# Microcontroller_and_Memory.net
KiCad netlist of a schematic drawn in Altium Designer
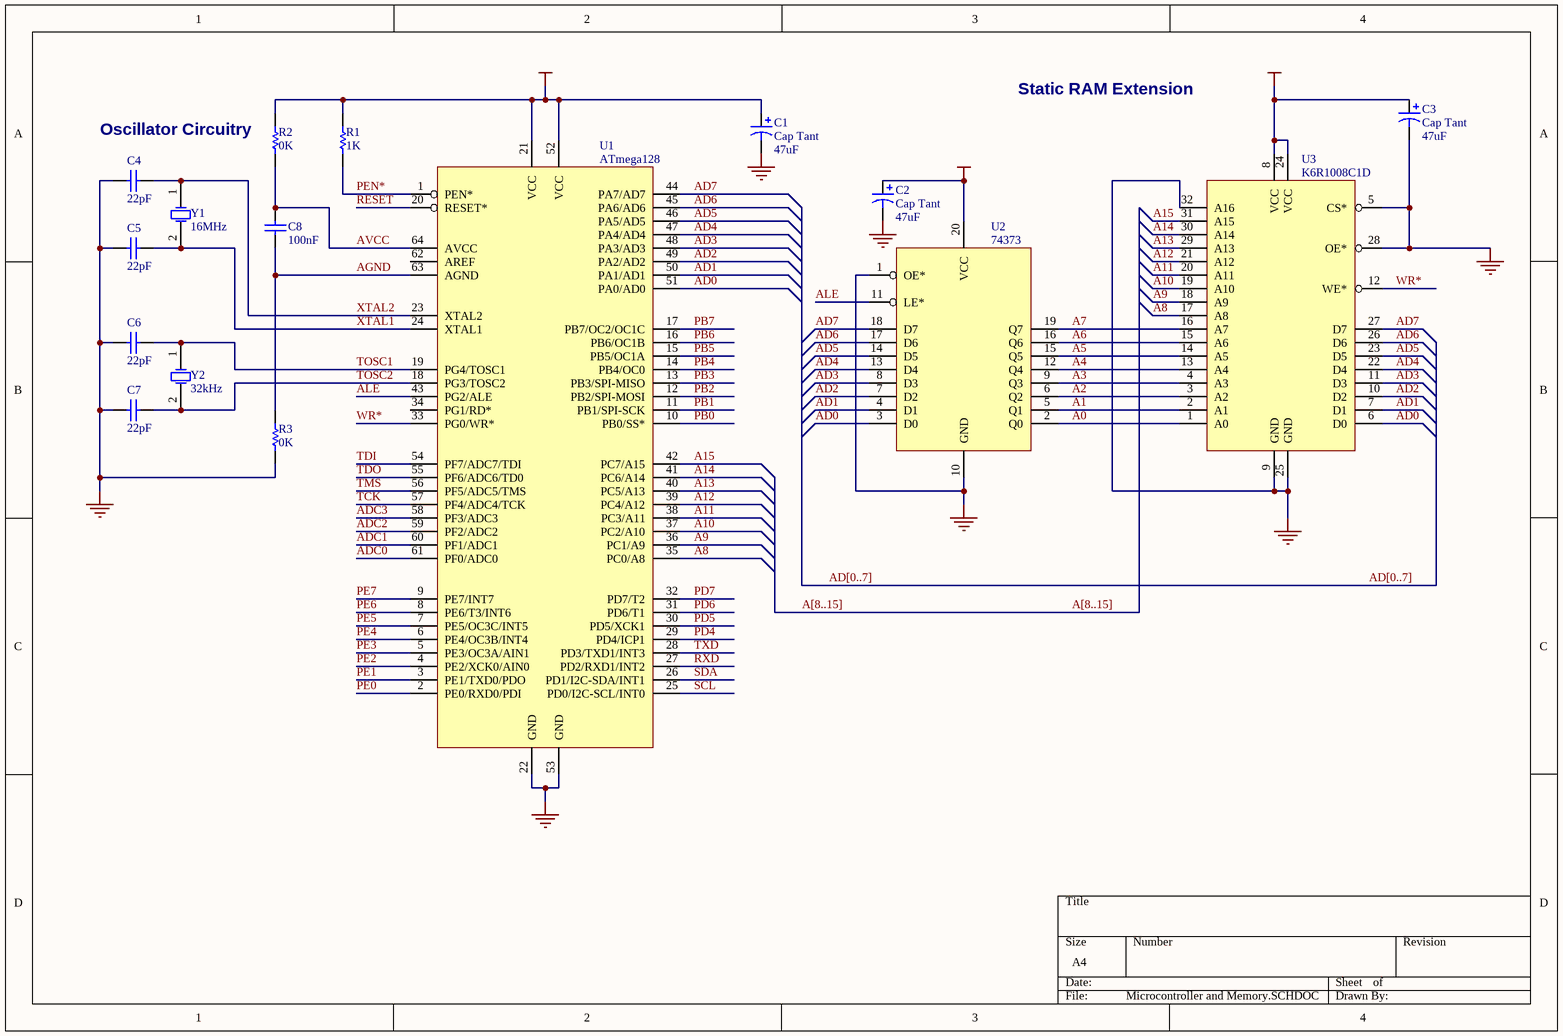
[diagram p0: Microcontroller and Memory.SCHDOC]

(export (version "E")
  (design (tool "Eeschema 10.0.6"))
  (components
    (comp (ref "C1")
      (value "Cap Tant")
      (footprint "CAPR5-4X5")
      (description "Polarized Capacitor (Axial)")
      (fields (field (name "ALTIUM_VALUE") "47uF") (field (name "PUBLISHER") "Altium Limited"))
      (libsource (lib "Miscellaneous Devices") (part "Cap Pol2"))
    )
    (comp (ref "C2")
      (value "Cap Tant")
      (footprint "CAPR5-4X5")
      (description "Polarized Capacitor (Axial)")
      (fields (field (name "ALTIUM_VALUE") "47uF") (field (name "PUBLISHER") "Altium Limited"))
      (libsource (lib "Miscellaneous Devices") (part "Cap Pol2"))
    )
    (comp (ref "C3")
      (value "Cap Tant")
      (footprint "CAPR5-4X5")
      (description "Polarized Capacitor (Axial)")
      (fields (field (name "ALTIUM_VALUE") "47uF") (field (name "PUBLISHER") "Altium Limited"))
      (libsource (lib "Miscellaneous Devices") (part "Cap Pol2"))
    )
    (comp (ref "C4")
      (value "22pF")
      (footprint "BCY-W2/D3.1")
      (description "Capacitor")
      (fields (field (name "PUBLISHER") "Altium Limited"))
      (libsource (lib "Miscellaneous Devices") (part "Cap"))
    )
    (comp (ref "C5")
      (value "22pF")
      (footprint "BCY-W2/D3.1")
      (description "Capacitor")
      (fields (field (name "PUBLISHER") "Altium Limited"))
      (libsource (lib "Miscellaneous Devices") (part "Cap"))
    )
    (comp (ref "C6")
      (value "22pF")
      (footprint "BCY-W2/D3.1")
      (description "Capacitor")
      (fields (field (name "PUBLISHER") "Altium Limited"))
      (libsource (lib "Miscellaneous Devices") (part "Cap"))
    )
    (comp (ref "C7")
      (value "22pF")
      (footprint "BCY-W2/D3.1")
      (description "Capacitor")
      (fields (field (name "PUBLISHER") "Altium Limited"))
      (libsource (lib "Miscellaneous Devices") (part "Cap"))
    )
    (comp (ref "C8")
      (value "100nF")
      (footprint "BCY-W2/D3.1")
      (description "Capacitor")
      (fields (field (name "PUBLISHER") "Altium Limited"))
      (libsource (lib "Miscellaneous Devices") (part "Cap"))
    )
    (comp (ref "R1")
      (value "1K")
      (footprint "AXIAL-0.3")
      (description "Resistor")
      (fields (field (name "PUBLISHER") "Altium Limited"))
      (libsource (lib "Miscellaneous Devices") (part "Res1"))
    )
    (comp (ref "R2")
      (value "0K")
      (footprint "AXIAL-0.3")
      (description "Resistor")
      (fields (field (name "PUBLISHER") "Altium Limited"))
      (libsource (lib "Miscellaneous Devices") (part "Res1"))
    )
    (comp (ref "R3")
      (value "0K")
      (footprint "AXIAL-0.3")
      (description "Resistor")
      (fields (field (name "PUBLISHER") "Altium Limited"))
      (libsource (lib "Miscellaneous Devices") (part "Res1"))
    )
    (comp (ref "U1")
      (value "ATmega128")
      (footprint "QFP (~0.8mm Pitch, Square) - Corner Index:QFP14x14-G64/Y1.4N")
      (description "Atmel ATmega128 MCU")
      (libsource (lib "*") (part "ATmega128"))
    )
    (comp (ref "U2")
      (value "74373")
      (footprint "SO-G20/Y1.45")
      (description "Octal 8-bit D-type Latch")
      (libsource (lib "Schematic Library") (part "74373"))
    )
    (comp (ref "U3")
      (value "K6R1008C1D")
      (footprint "SO-G32/Y1.45")
      (description "Samsung 128Kx8 High-Speed Static RAM")
      (libsource (lib "Schematic Library") (part "K6R1008C1D"))
    )
    (comp (ref "Y1")
      (value "16MHz")
      (footprint "BCY-W2/D3.1")
      (description "Crystal Oscillator")
      (fields (field (name "PUBLISHER") "Altium Limited"))
      (libsource (lib "Miscellaneous Devices") (part "XTAL"))
    )
    (comp (ref "Y2")
      (value "32kHz")
      (footprint "BCY-W2/D3.1")
      (description "Crystal Oscillator")
      (fields (field (name "PUBLISHER") "Altium Limited"))
      (libsource (lib "Miscellaneous Devices") (part "XTAL"))
    )
  )
  (nets
    (net (code "1") (name "/A0") (class "Default")
      (node (ref "U2") (pin "2") (pinfunction "Q0_2") (pintype "passive"))
      (node (ref "U3") (pin "1") (pinfunction "A0_1") (pintype "passive"))
    )
    (net (code "2") (name "/A1") (class "Default")
      (node (ref "U2") (pin "5") (pinfunction "Q1_5") (pintype "passive"))
      (node (ref "U3") (pin "2") (pinfunction "A1_2") (pintype "passive"))
    )
    (net (code "3") (name "/A2") (class "Default")
      (node (ref "U2") (pin "6") (pinfunction "Q2_6") (pintype "passive"))
      (node (ref "U3") (pin "3") (pinfunction "A2_3") (pintype "passive"))
    )
    (net (code "4") (name "/A3") (class "Default")
      (node (ref "U2") (pin "9") (pinfunction "Q3_9") (pintype "passive"))
      (node (ref "U3") (pin "4") (pinfunction "A3_4") (pintype "passive"))
    )
    (net (code "5") (name "/A4") (class "Default")
      (node (ref "U2") (pin "12") (pinfunction "Q4_12") (pintype "passive"))
      (node (ref "U3") (pin "13") (pinfunction "A4_13") (pintype "passive"))
    )
    (net (code "6") (name "/A5") (class "Default")
      (node (ref "U2") (pin "15") (pinfunction "Q5_15") (pintype "passive"))
      (node (ref "U3") (pin "14") (pinfunction "A5_14") (pintype "passive"))
    )
    (net (code "7") (name "/A6") (class "Default")
      (node (ref "U2") (pin "16") (pinfunction "Q6_16") (pintype "passive"))
      (node (ref "U3") (pin "15") (pinfunction "A6_15") (pintype "passive"))
    )
    (net (code "8") (name "/A7") (class "Default")
      (node (ref "U2") (pin "19") (pinfunction "Q7_19") (pintype "passive"))
      (node (ref "U3") (pin "16") (pinfunction "A7_16") (pintype "passive"))
    )
    (net (code "9") (name "/A8") (class "Default")
      (node (ref "U1") (pin "35") (pinfunction "PC0/A8_35") (pintype "passive"))
      (node (ref "U3") (pin "17") (pinfunction "A8_17") (pintype "passive"))
    )
    (net (code "10") (name "/A9") (class "Default")
      (node (ref "U1") (pin "36") (pinfunction "PC1/A9_36") (pintype "passive"))
      (node (ref "U3") (pin "18") (pinfunction "A9_18") (pintype "passive"))
    )
    (net (code "11") (name "/A10") (class "Default")
      (node (ref "U1") (pin "37") (pinfunction "PC2/A10_37") (pintype "passive"))
      (node (ref "U3") (pin "19") (pinfunction "A10_19") (pintype "passive"))
    )
    (net (code "12") (name "/A11") (class "Default")
      (node (ref "U1") (pin "38") (pinfunction "PC3/A11_38") (pintype "passive"))
      (node (ref "U3") (pin "20") (pinfunction "A11_20") (pintype "passive"))
    )
    (net (code "13") (name "/A12") (class "Default")
      (node (ref "U1") (pin "39") (pinfunction "PC4/A12_39") (pintype "passive"))
      (node (ref "U3") (pin "21") (pinfunction "A12_21") (pintype "passive"))
    )
    (net (code "14") (name "/A13") (class "Default")
      (node (ref "U1") (pin "40") (pinfunction "PC5/A13_40") (pintype "passive"))
      (node (ref "U3") (pin "29") (pinfunction "A13_29") (pintype "passive"))
    )
    (net (code "15") (name "/A14") (class "Default")
      (node (ref "U1") (pin "41") (pinfunction "PC6/A14_41") (pintype "passive"))
      (node (ref "U3") (pin "30") (pinfunction "A14_30") (pintype "passive"))
    )
    (net (code "16") (name "/A15") (class "Default")
      (node (ref "U1") (pin "42") (pinfunction "PC7/A15_42") (pintype "passive"))
      (node (ref "U3") (pin "31") (pinfunction "A15_31") (pintype "passive"))
    )
    (net (code "17") (name "/AD0") (class "Default")
      (node (ref "U1") (pin "51") (pinfunction "PA0/AD0_51") (pintype "passive"))
      (node (ref "U2") (pin "3") (pinfunction "D0_3") (pintype "passive"))
      (node (ref "U3") (pin "6") (pinfunction "D0_6") (pintype "passive"))
    )
    (net (code "18") (name "/AD1") (class "Default")
      (node (ref "U1") (pin "50") (pinfunction "PA1/AD1_50") (pintype "passive"))
      (node (ref "U2") (pin "4") (pinfunction "D1_4") (pintype "passive"))
      (node (ref "U3") (pin "7") (pinfunction "D1_7") (pintype "passive"))
    )
    (net (code "19") (name "/AD2") (class "Default")
      (node (ref "U1") (pin "49") (pinfunction "PA2/AD2_49") (pintype "passive"))
      (node (ref "U2") (pin "7") (pinfunction "D2_7") (pintype "passive"))
      (node (ref "U3") (pin "10") (pinfunction "D2_10") (pintype "passive"))
    )
    (net (code "20") (name "/AD3") (class "Default")
      (node (ref "U1") (pin "48") (pinfunction "PA3/AD3_48") (pintype "passive"))
      (node (ref "U2") (pin "8") (pinfunction "D3_8") (pintype "passive"))
      (node (ref "U3") (pin "11") (pinfunction "D3_11") (pintype "passive"))
    )
    (net (code "21") (name "/AD4") (class "Default")
      (node (ref "U1") (pin "47") (pinfunction "PA4/AD4_47") (pintype "passive"))
      (node (ref "U2") (pin "13") (pinfunction "D4_13") (pintype "passive"))
      (node (ref "U3") (pin "22") (pinfunction "D4_22") (pintype "passive"))
    )
    (net (code "22") (name "/AD5") (class "Default")
      (node (ref "U1") (pin "46") (pinfunction "PA5/AD5_46") (pintype "passive"))
      (node (ref "U2") (pin "14") (pinfunction "D5_14") (pintype "passive"))
      (node (ref "U3") (pin "23") (pinfunction "D5_23") (pintype "passive"))
    )
    (net (code "23") (name "/AD6") (class "Default")
      (node (ref "U1") (pin "45") (pinfunction "PA6/AD6_45") (pintype "passive"))
      (node (ref "U2") (pin "17") (pinfunction "D6_17") (pintype "passive"))
      (node (ref "U3") (pin "26") (pinfunction "D6_26") (pintype "passive"))
    )
    (net (code "24") (name "/AD7") (class "Default")
      (node (ref "U1") (pin "44") (pinfunction "PA7/AD7_44") (pintype "passive"))
      (node (ref "U2") (pin "18") (pinfunction "D7_18") (pintype "passive"))
      (node (ref "U3") (pin "27") (pinfunction "D7_27") (pintype "passive"))
    )
    (net (code "25") (name "/ADC0") (class "Default")
      (node (ref "U1") (pin "61") (pinfunction "PF0/ADC0_61") (pintype "passive"))
    )
    (net (code "26") (name "/ADC1") (class "Default")
      (node (ref "U1") (pin "60") (pinfunction "PF1/ADC1_60") (pintype "passive"))
    )
    (net (code "27") (name "/ADC2") (class "Default")
      (node (ref "U1") (pin "59") (pinfunction "PF2/ADC2_59") (pintype "passive"))
    )
    (net (code "28") (name "/ADC3") (class "Default")
      (node (ref "U1") (pin "58") (pinfunction "PF3/ADC3_58") (pintype "passive"))
    )
    (net (code "30") (name "/AGND") (class "Default")
      (node (ref "C8") (pin "1") (pinfunction "1_1") (pintype "passive"))
      (node (ref "R3") (pin "2") (pinfunction "2_2") (pintype "passive"))
      (node (ref "U1") (pin "63") (pinfunction "AGND_63") (pintype "passive"))
    )
    (net (code "31") (name "/ALE") (class "Default")
      (node (ref "U1") (pin "43") (pinfunction "PG2/ALE_43") (pintype "passive"))
      (node (ref "U2") (pin "11") (pinfunction "LE*_11") (pintype "passive"))
    )
    (net (code "32") (name "/AVCC") (class "Default")
      (node (ref "C8") (pin "2") (pinfunction "2_2") (pintype "passive"))
      (node (ref "R2") (pin "1") (pinfunction "1_1") (pintype "passive"))
      (node (ref "U1") (pin "64") (pinfunction "AVCC_64") (pintype "passive"))
    )
    (net (code "34") (name "/PB0") (class "Default")
      (node (ref "U1") (pin "10") (pinfunction "PB0/SS*_10") (pintype "passive"))
    )
    (net (code "35") (name "/PB1") (class "Default")
      (node (ref "U1") (pin "11") (pinfunction "PB1/SPI-SCK_11") (pintype "passive"))
    )
    (net (code "36") (name "/PB2") (class "Default")
      (node (ref "U1") (pin "12") (pinfunction "PB2/SPI-MOSI_12") (pintype "passive"))
    )
    (net (code "37") (name "/PB3") (class "Default")
      (node (ref "U1") (pin "13") (pinfunction "PB3/SPI-MISO_13") (pintype "passive"))
    )
    (net (code "38") (name "/PB4") (class "Default")
      (node (ref "U1") (pin "14") (pinfunction "PB4/OC0_14") (pintype "passive"))
    )
    (net (code "39") (name "/PB5") (class "Default")
      (node (ref "U1") (pin "15") (pinfunction "PB5/OC1A_15") (pintype "passive"))
    )
    (net (code "40") (name "/PB6") (class "Default")
      (node (ref "U1") (pin "16") (pinfunction "PB6/OC1B_16") (pintype "passive"))
    )
    (net (code "41") (name "/PB7") (class "Default")
      (node (ref "U1") (pin "17") (pinfunction "PB7/OC2/OC1C_17") (pintype "passive"))
    )
    (net (code "42") (name "/PD4") (class "Default")
      (node (ref "U1") (pin "29") (pinfunction "PD4/ICP1_29") (pintype "passive"))
    )
    (net (code "43") (name "/PD5") (class "Default")
      (node (ref "U1") (pin "30") (pinfunction "PD5/XCK1_30") (pintype "passive"))
    )
    (net (code "44") (name "/PD6") (class "Default")
      (node (ref "U1") (pin "31") (pinfunction "PD6/T1_31") (pintype "passive"))
    )
    (net (code "45") (name "/PD7") (class "Default")
      (node (ref "U1") (pin "32") (pinfunction "PD7/T2_32") (pintype "passive"))
    )
    (net (code "46") (name "/PE0") (class "Default")
      (node (ref "U1") (pin "2") (pinfunction "PE0/RXD0/PDI_2") (pintype "passive"))
    )
    (net (code "47") (name "/PE1") (class "Default")
      (node (ref "U1") (pin "3") (pinfunction "PE1/TXD0/PDO_3") (pintype "passive"))
    )
    (net (code "48") (name "/PE2") (class "Default")
      (node (ref "U1") (pin "4") (pinfunction "PE2/XCK0/AIN0_4") (pintype "passive"))
    )
    (net (code "49") (name "/PE3") (class "Default")
      (node (ref "U1") (pin "5") (pinfunction "PE3/OC3A/AIN1_5") (pintype "passive"))
    )
    (net (code "50") (name "/PE4") (class "Default")
      (node (ref "U1") (pin "6") (pinfunction "PE4/OC3B/INT4_6") (pintype "passive"))
    )
    (net (code "51") (name "/PE5") (class "Default")
      (node (ref "U1") (pin "7") (pinfunction "PE5/OC3C/INT5_7") (pintype "passive"))
    )
    (net (code "52") (name "/PE6") (class "Default")
      (node (ref "U1") (pin "8") (pinfunction "PE6/T3/INT6_8") (pintype "passive"))
    )
    (net (code "53") (name "/PE7") (class "Default")
      (node (ref "U1") (pin "9") (pinfunction "PE7/INT7_9") (pintype "passive"))
    )
    (net (code "54") (name "/PEN*") (class "Default")
      (node (ref "R1") (pin "1") (pinfunction "1_1") (pintype "passive"))
      (node (ref "U1") (pin "1") (pinfunction "PEN*_1") (pintype "passive"))
    )
    (net (code "55") (name "/RESET") (class "Default")
      (node (ref "U1") (pin "20") (pinfunction "RESET*_20") (pintype "passive"))
    )
    (net (code "56") (name "/RXD") (class "Default")
      (node (ref "U1") (pin "27") (pinfunction "PD2/RXD1/INT2_27") (pintype "passive"))
    )
    (net (code "57") (name "/SCL") (class "Default")
      (node (ref "U1") (pin "25") (pinfunction "PD0/I2C-SCL/INT0_25") (pintype "passive"))
    )
    (net (code "58") (name "/SDA") (class "Default")
      (node (ref "U1") (pin "26") (pinfunction "PD1/I2C-SDA/INT1_26") (pintype "passive"))
    )
    (net (code "59") (name "/TCK") (class "Default")
      (node (ref "U1") (pin "57") (pinfunction "PF4/ADC4/TCK_57") (pintype "passive"))
    )
    (net (code "60") (name "/TDI") (class "Default")
      (node (ref "U1") (pin "54") (pinfunction "PF7/ADC7/TDI_54") (pintype "passive"))
    )
    (net (code "61") (name "/TDO") (class "Default")
      (node (ref "U1") (pin "55") (pinfunction "PF6/ADC6/TD0_55") (pintype "passive"))
    )
    (net (code "62") (name "/TMS") (class "Default")
      (node (ref "U1") (pin "56") (pinfunction "PF5/ADC5/TMS_56") (pintype "passive"))
    )
    (net (code "63") (name "/TOSC1") (class "Default")
      (node (ref "C6") (pin "2") (pinfunction "2_2") (pintype "passive"))
      (node (ref "U1") (pin "19") (pinfunction "PG4/TOSC1_19") (pintype "passive"))
      (node (ref "Y2") (pin "1") (pinfunction "OSC1_1") (pintype "passive"))
    )
    (net (code "64") (name "/TOSC2") (class "Default")
      (node (ref "C7") (pin "2") (pinfunction "2_2") (pintype "passive"))
      (node (ref "U1") (pin "18") (pinfunction "PG3/TOSC2_18") (pintype "passive"))
      (node (ref "Y2") (pin "2") (pinfunction "OSC2_2") (pintype "passive"))
    )
    (net (code "65") (name "/TXD") (class "Default")
      (node (ref "U1") (pin "28") (pinfunction "PD3/TXD1/INT3_28") (pintype "passive"))
    )
    (net (code "66") (name "/WR*") (class "Default")
      (node (ref "U1") (pin "33") (pinfunction "PG0/WR*_33") (pintype "passive"))
      (node (ref "U3") (pin "12") (pinfunction "WE*_12") (pintype "passive"))
    )
    (net (code "67") (name "/XTAL1") (class "Default")
      (node (ref "C5") (pin "2") (pinfunction "2_2") (pintype "passive"))
      (node (ref "U1") (pin "24") (pinfunction "XTAL1_24") (pintype "passive"))
      (node (ref "Y1") (pin "2") (pinfunction "OSC2_2") (pintype "passive"))
    )
    (net (code "68") (name "/XTAL2") (class "Default")
      (node (ref "C4") (pin "2") (pinfunction "2_2") (pintype "passive"))
      (node (ref "U1") (pin "23") (pinfunction "XTAL2_23") (pintype "passive"))
      (node (ref "Y1") (pin "1") (pinfunction "OSC1_1") (pintype "passive"))
    )
    (net (code "69") (name "5V") (class "Default")
      (node (ref "C1") (pin "1") (pinfunction "1_1") (pintype "passive"))
      (node (ref "C2") (pin "1") (pinfunction "1_1") (pintype "passive"))
      (node (ref "C3") (pin "1") (pinfunction "1_1") (pintype "passive"))
      (node (ref "R1") (pin "2") (pinfunction "2_2") (pintype "passive"))
      (node (ref "R2") (pin "2") (pinfunction "2_2") (pintype "passive"))
      (node (ref "U1") (pin "21") (pinfunction "VCC_21") (pintype "passive"))
      (node (ref "U1") (pin "52") (pinfunction "VCC_52") (pintype "passive"))
      (node (ref "U2") (pin "20") (pinfunction "VCC_20") (pintype "passive"))
      (node (ref "U3") (pin "24") (pinfunction "VCC_24") (pintype "passive"))
      (node (ref "U3") (pin "8") (pinfunction "VCC_8") (pintype "passive"))
    )
    (net (code "70") (name "GND") (class "Default")
      (node (ref "C1") (pin "2") (pinfunction "2_2") (pintype "passive"))
      (node (ref "C2") (pin "2") (pinfunction "2_2") (pintype "passive"))
      (node (ref "C3") (pin "2") (pinfunction "2_2") (pintype "passive"))
      (node (ref "C4") (pin "1") (pinfunction "1_1") (pintype "passive"))
      (node (ref "C5") (pin "1") (pinfunction "1_1") (pintype "passive"))
      (node (ref "C6") (pin "1") (pinfunction "1_1") (pintype "passive"))
      (node (ref "C7") (pin "1") (pinfunction "1_1") (pintype "passive"))
      (node (ref "R3") (pin "1") (pinfunction "1_1") (pintype "passive"))
      (node (ref "U1") (pin "22") (pinfunction "GND_22") (pintype "passive"))
      (node (ref "U1") (pin "53") (pinfunction "GND_53") (pintype "passive"))
      (node (ref "U2") (pin "1") (pinfunction "OE*_1") (pintype "passive"))
      (node (ref "U2") (pin "10") (pinfunction "GND_10") (pintype "passive"))
      (node (ref "U3") (pin "25") (pinfunction "GND_25") (pintype "passive"))
      (node (ref "U3") (pin "28") (pinfunction "OE*_28") (pintype "passive"))
      (node (ref "U3") (pin "32") (pinfunction "A16_32") (pintype "passive"))
      (node (ref "U3") (pin "5") (pinfunction "CS*_5") (pintype "passive"))
      (node (ref "U3") (pin "9") (pinfunction "GND_9") (pintype "passive"))
    )
    (net (code "71") (name "unconnected-(U1-AREF-Pad62)") (class "Default")
      (node (ref "U1") (pin "62") (pinfunction "AREF_62") (pintype "passive"))
    )
    (net (code "72") (name "unconnected-(U1-PG1{slash}RD*-Pad34)") (class "Default")
      (node (ref "U1") (pin "34") (pinfunction "PG1/RD*_34") (pintype "passive"))
    )
  )
)
